# SolarCellX.net
KiCad netlist of a schematic drawn in EAGLE
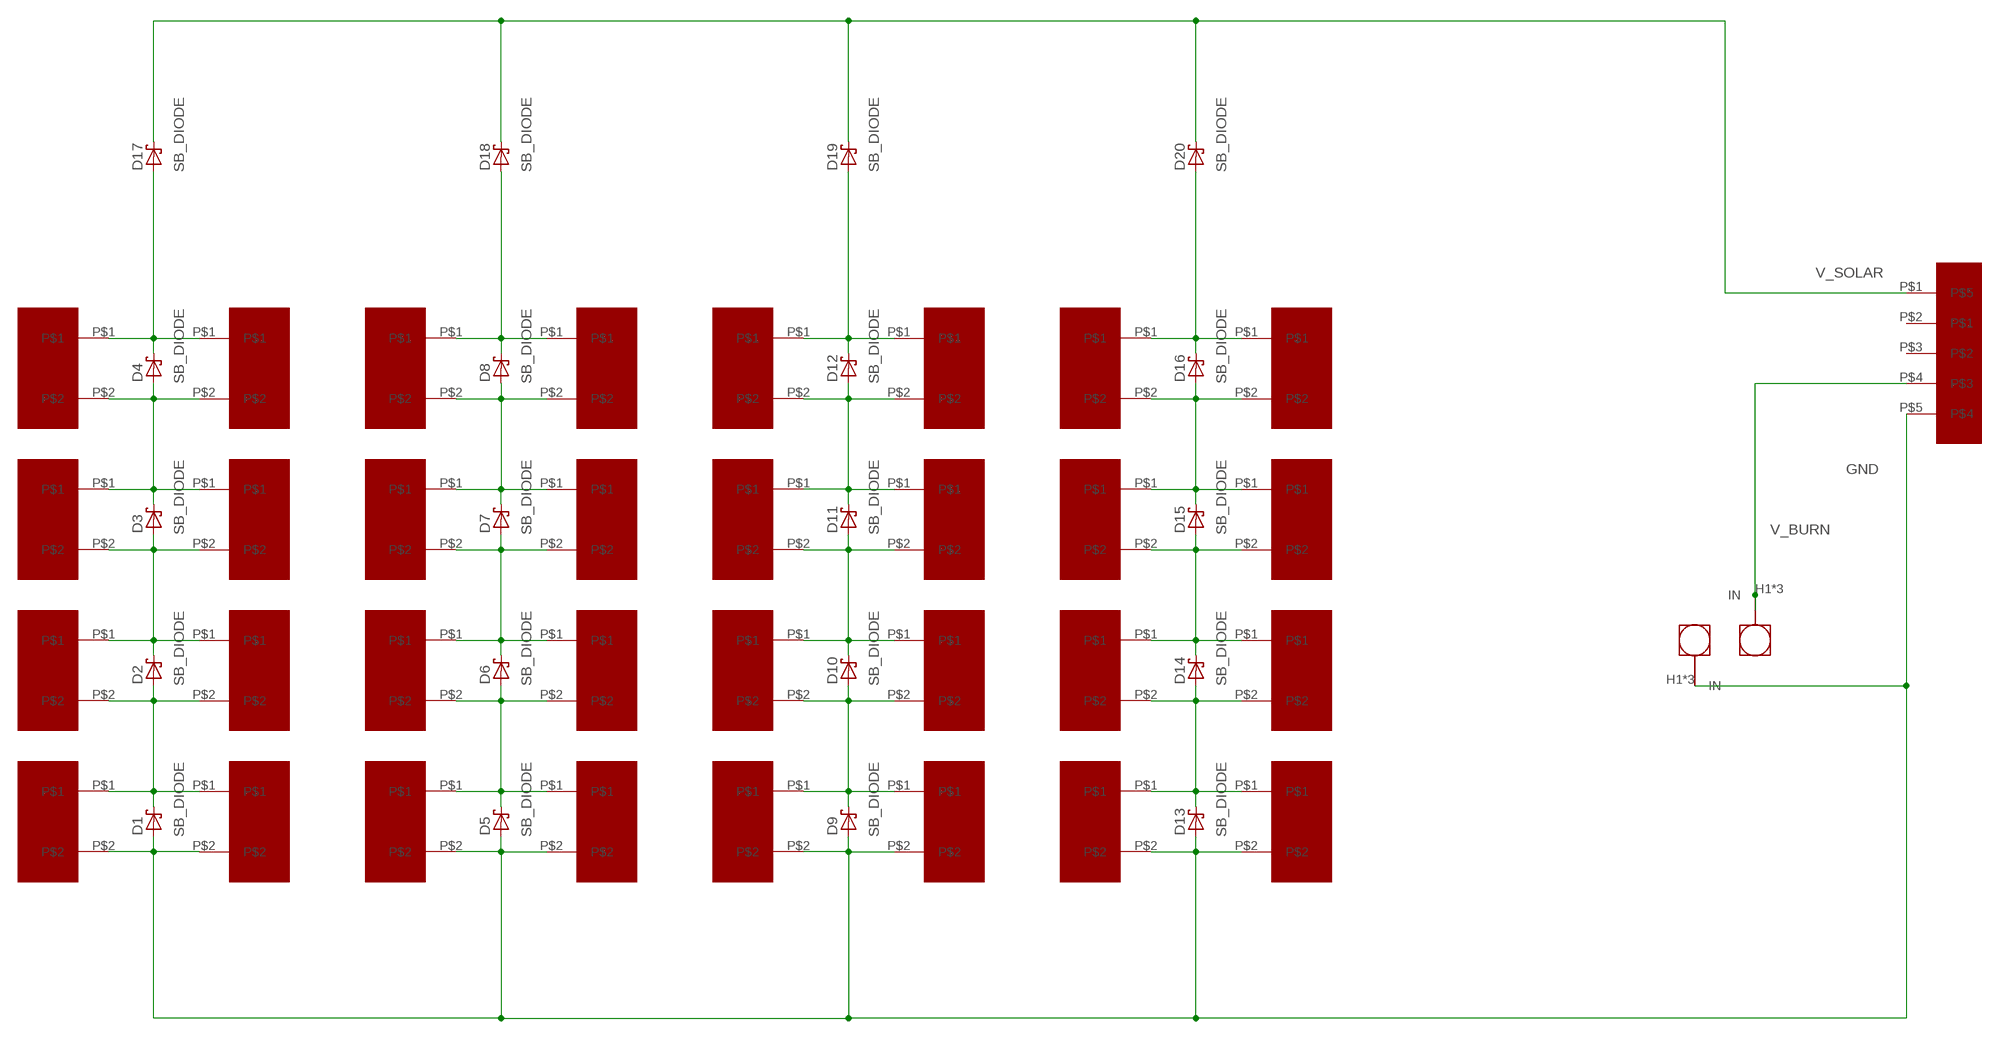
[diagram p0: schematic, sheet 1]

(export (version "E")
  (design (tool "Eeschema 10.0.6"))
  (components
    (comp (ref "11")
      (value "KXOB22-04X3F")
      (footprint "eagle-import:KXOB22-04X3F")
      (libsource (lib "eagle-import") (part "KXOB22-04X3F"))
    )
    (comp (ref "12")
      (value "KXOB22-04X3F")
      (footprint "eagle-import:KXOB22-04X3F")
      (libsource (lib "eagle-import") (part "KXOB22-04X3F"))
    )
    (comp (ref "13")
      (value "KXOB22-04X3F")
      (footprint "eagle-import:KXOB22-04X3F")
      (libsource (lib "eagle-import") (part "KXOB22-04X3F"))
    )
    (comp (ref "14")
      (value "KXOB22-04X3F")
      (footprint "eagle-import:KXOB22-04X3F")
      (libsource (lib "eagle-import") (part "KXOB22-04X3F"))
    )
    (comp (ref "15")
      (value "KXOB22-04X3F")
      (footprint "eagle-import:KXOB22-04X3F")
      (libsource (lib "eagle-import") (part "KXOB22-04X3F"))
    )
    (comp (ref "16")
      (value "KXOB22-04X3F")
      (footprint "eagle-import:KXOB22-04X3F")
      (libsource (lib "eagle-import") (part "KXOB22-04X3F"))
    )
    (comp (ref "17")
      (value "KXOB22-04X3F")
      (footprint "eagle-import:KXOB22-04X3F")
      (libsource (lib "eagle-import") (part "KXOB22-04X3F"))
    )
    (comp (ref "18")
      (value "KXOB22-04X3F")
      (footprint "eagle-import:KXOB22-04X3F")
      (libsource (lib "eagle-import") (part "KXOB22-04X3F"))
    )
    (comp (ref "21")
      (value "KXOB22-04X3F")
      (footprint "eagle-import:KXOB22-04X3F")
      (libsource (lib "eagle-import") (part "KXOB22-04X3F"))
    )
    (comp (ref "22")
      (value "KXOB22-04X3F")
      (footprint "eagle-import:KXOB22-04X3F")
      (libsource (lib "eagle-import") (part "KXOB22-04X3F"))
    )
    (comp (ref "23")
      (value "KXOB22-04X3F")
      (footprint "eagle-import:KXOB22-04X3F")
      (libsource (lib "eagle-import") (part "KXOB22-04X3F"))
    )
    (comp (ref "24")
      (value "KXOB22-04X3F")
      (footprint "eagle-import:KXOB22-04X3F")
      (libsource (lib "eagle-import") (part "KXOB22-04X3F"))
    )
    (comp (ref "25")
      (value "KXOB22-04X3F")
      (footprint "eagle-import:KXOB22-04X3F")
      (libsource (lib "eagle-import") (part "KXOB22-04X3F"))
    )
    (comp (ref "26")
      (value "KXOB22-04X3F")
      (footprint "eagle-import:KXOB22-04X3F")
      (libsource (lib "eagle-import") (part "KXOB22-04X3F"))
    )
    (comp (ref "27")
      (value "KXOB22-04X3F")
      (footprint "eagle-import:KXOB22-04X3F")
      (libsource (lib "eagle-import") (part "KXOB22-04X3F"))
    )
    (comp (ref "28")
      (value "KXOB22-04X3F")
      (footprint "eagle-import:KXOB22-04X3F")
      (libsource (lib "eagle-import") (part "KXOB22-04X3F"))
    )
    (comp (ref "31")
      (value "KXOB22-04X3F")
      (footprint "eagle-import:KXOB22-04X3F")
      (libsource (lib "eagle-import") (part "KXOB22-04X3F"))
    )
    (comp (ref "32")
      (value "KXOB22-04X3F")
      (footprint "eagle-import:KXOB22-04X3F")
      (libsource (lib "eagle-import") (part "KXOB22-04X3F"))
    )
    (comp (ref "33")
      (value "KXOB22-04X3F")
      (footprint "eagle-import:KXOB22-04X3F")
      (libsource (lib "eagle-import") (part "KXOB22-04X3F"))
    )
    (comp (ref "34")
      (value "KXOB22-04X3F")
      (footprint "eagle-import:KXOB22-04X3F")
      (libsource (lib "eagle-import") (part "KXOB22-04X3F"))
    )
    (comp (ref "35")
      (value "KXOB22-04X3F")
      (footprint "eagle-import:KXOB22-04X3F")
      (libsource (lib "eagle-import") (part "KXOB22-04X3F"))
    )
    (comp (ref "36")
      (value "KXOB22-04X3F")
      (footprint "eagle-import:KXOB22-04X3F")
      (libsource (lib "eagle-import") (part "KXOB22-04X3F"))
    )
    (comp (ref "37")
      (value "KXOB22-04X3F")
      (footprint "eagle-import:KXOB22-04X3F")
      (libsource (lib "eagle-import") (part "KXOB22-04X3F"))
    )
    (comp (ref "38")
      (value "KXOB22-04X3F")
      (footprint "eagle-import:KXOB22-04X3F")
      (libsource (lib "eagle-import") (part "KXOB22-04X3F"))
    )
    (comp (ref "41")
      (value "KXOB22-04X3F")
      (footprint "eagle-import:KXOB22-04X3F")
      (libsource (lib "eagle-import") (part "KXOB22-04X3F"))
    )
    (comp (ref "42")
      (value "KXOB22-04X3F")
      (footprint "eagle-import:KXOB22-04X3F")
      (libsource (lib "eagle-import") (part "KXOB22-04X3F"))
    )
    (comp (ref "43")
      (value "KXOB22-04X3F")
      (footprint "eagle-import:KXOB22-04X3F")
      (libsource (lib "eagle-import") (part "KXOB22-04X3F"))
    )
    (comp (ref "44")
      (value "KXOB22-04X3F")
      (footprint "eagle-import:KXOB22-04X3F")
      (libsource (lib "eagle-import") (part "KXOB22-04X3F"))
    )
    (comp (ref "45")
      (value "KXOB22-04X3F")
      (footprint "eagle-import:KXOB22-04X3F")
      (libsource (lib "eagle-import") (part "KXOB22-04X3F"))
    )
    (comp (ref "46")
      (value "KXOB22-04X3F")
      (footprint "eagle-import:KXOB22-04X3F")
      (libsource (lib "eagle-import") (part "KXOB22-04X3F"))
    )
    (comp (ref "47")
      (value "KXOB22-04X3F")
      (footprint "eagle-import:KXOB22-04X3F")
      (libsource (lib "eagle-import") (part "KXOB22-04X3F"))
    )
    (comp (ref "48")
      (value "KXOB22-04X3F")
      (footprint "eagle-import:KXOB22-04X3F")
      (libsource (lib "eagle-import") (part "KXOB22-04X3F"))
    )
    (comp (ref "D1")
      (value "SB_DIODE")
      (footprint "eagle-import:SB_DIODE")
      (libsource (lib "eagle-import") (part "SB_DIODE"))
    )
    (comp (ref "D2")
      (value "SB_DIODE")
      (footprint "eagle-import:SB_DIODE")
      (libsource (lib "eagle-import") (part "SB_DIODE"))
    )
    (comp (ref "D3")
      (value "SB_DIODE")
      (footprint "eagle-import:SB_DIODE")
      (libsource (lib "eagle-import") (part "SB_DIODE"))
    )
    (comp (ref "D4")
      (value "SB_DIODE")
      (footprint "eagle-import:SB_DIODE")
      (libsource (lib "eagle-import") (part "SB_DIODE"))
    )
    (comp (ref "D5")
      (value "SB_DIODE")
      (footprint "eagle-import:SB_DIODE")
      (libsource (lib "eagle-import") (part "SB_DIODE"))
    )
    (comp (ref "D6")
      (value "SB_DIODE")
      (footprint "eagle-import:SB_DIODE")
      (libsource (lib "eagle-import") (part "SB_DIODE"))
    )
    (comp (ref "D7")
      (value "SB_DIODE")
      (footprint "eagle-import:SB_DIODE")
      (libsource (lib "eagle-import") (part "SB_DIODE"))
    )
    (comp (ref "D8")
      (value "SB_DIODE")
      (footprint "eagle-import:SB_DIODE")
      (libsource (lib "eagle-import") (part "SB_DIODE"))
    )
    (comp (ref "D9")
      (value "SB_DIODE")
      (footprint "eagle-import:SB_DIODE")
      (libsource (lib "eagle-import") (part "SB_DIODE"))
    )
    (comp (ref "D10")
      (value "SB_DIODE")
      (footprint "eagle-import:SB_DIODE")
      (libsource (lib "eagle-import") (part "SB_DIODE"))
    )
    (comp (ref "D11")
      (value "SB_DIODE")
      (footprint "eagle-import:SB_DIODE")
      (libsource (lib "eagle-import") (part "SB_DIODE"))
    )
    (comp (ref "D12")
      (value "SB_DIODE")
      (footprint "eagle-import:SB_DIODE")
      (libsource (lib "eagle-import") (part "SB_DIODE"))
    )
    (comp (ref "D13")
      (value "SB_DIODE")
      (footprint "eagle-import:SB_DIODE")
      (libsource (lib "eagle-import") (part "SB_DIODE"))
    )
    (comp (ref "D14")
      (value "SB_DIODE")
      (footprint "eagle-import:SB_DIODE")
      (libsource (lib "eagle-import") (part "SB_DIODE"))
    )
    (comp (ref "D15")
      (value "SB_DIODE")
      (footprint "eagle-import:SB_DIODE")
      (libsource (lib "eagle-import") (part "SB_DIODE"))
    )
    (comp (ref "D16")
      (value "SB_DIODE")
      (footprint "eagle-import:SB_DIODE")
      (libsource (lib "eagle-import") (part "SB_DIODE"))
    )
    (comp (ref "D17")
      (value "SB_DIODE")
      (footprint "eagle-import:SB_DIODE")
      (libsource (lib "eagle-import") (part "SB_DIODE"))
    )
    (comp (ref "D18")
      (value "SB_DIODE")
      (footprint "eagle-import:SB_DIODE")
      (libsource (lib "eagle-import") (part "SB_DIODE"))
    )
    (comp (ref "D19")
      (value "SB_DIODE")
      (footprint "eagle-import:SB_DIODE")
      (libsource (lib "eagle-import") (part "SB_DIODE"))
    )
    (comp (ref "D20")
      (value "SB_DIODE")
      (footprint "eagle-import:SB_DIODE")
      (libsource (lib "eagle-import") (part "SB_DIODE"))
    )
    (comp (ref "U$33")
      (value "B5B-EH-A(LF)(SN)")
      (footprint "eagle-import:B5B-EH-A(LF)(SN)")
      (libsource (lib "eagle-import") (part "B5B-EH-A(LF)(SN)"))
    )
    (comp (ref "U$34")
      (value "BURNER")
      (footprint "eagle-import:BURNER")
      (libsource (lib "eagle-import") (part "BURNER"))
    )
    (comp (ref "U$35")
      (value "BURNER")
      (footprint "eagle-import:BURNER")
      (libsource (lib "eagle-import") (part "BURNER"))
    )
  )
  (nets
    (net (code "1") (name "/GND") (class "Default")
      (node (ref "11") (pin "P$2") (pinfunction "P$2_P$2") (pintype "bidirectional"))
      (node (ref "12") (pin "P$2") (pinfunction "P$2_P$2") (pintype "bidirectional"))
      (node (ref "21") (pin "P$2") (pinfunction "P$2_P$2") (pintype "bidirectional"))
      (node (ref "22") (pin "P$2") (pinfunction "P$2_P$2") (pintype "bidirectional"))
      (node (ref "31") (pin "P$2") (pinfunction "P$2_P$2") (pintype "bidirectional"))
      (node (ref "32") (pin "P$2") (pinfunction "P$2_P$2") (pintype "bidirectional"))
      (node (ref "41") (pin "P$2") (pinfunction "P$2_P$2") (pintype "bidirectional"))
      (node (ref "42") (pin "P$2") (pinfunction "P$2_P$2") (pintype "bidirectional"))
      (node (ref "D1") (pin "POS") (pinfunction "POS_POS") (pintype "passive"))
      (node (ref "D13") (pin "POS") (pinfunction "POS_POS") (pintype "passive"))
      (node (ref "D5") (pin "POS") (pinfunction "POS_POS") (pintype "passive"))
      (node (ref "D9") (pin "POS") (pinfunction "POS_POS") (pintype "passive"))
      (node (ref "U$33") (pin "P$5") (pinfunction "P$4_P$5") (pintype "bidirectional"))
      (node (ref "U$35") (pin "H1") (pinfunction "IN_H1") (pintype "bidirectional"))
      (node (ref "U$35") (pin "H2") (pinfunction "IN_H2") (pintype "bidirectional"))
      (node (ref "U$35") (pin "H3") (pinfunction "IN_H3") (pintype "bidirectional"))
    )
    (net (code "2") (name "/V_BURN") (class "Default")
      (node (ref "U$33") (pin "P$4") (pinfunction "P$3_P$4") (pintype "bidirectional"))
      (node (ref "U$34") (pin "H1") (pinfunction "IN_H1") (pintype "bidirectional"))
      (node (ref "U$34") (pin "H2") (pinfunction "IN_H2") (pintype "bidirectional"))
      (node (ref "U$34") (pin "H3") (pinfunction "IN_H3") (pintype "bidirectional"))
    )
    (net (code "3") (name "/V_SOLAR") (class "Default")
      (node (ref "D17") (pin "NEG") (pinfunction "NEG_NEG") (pintype "passive"))
      (node (ref "D18") (pin "NEG") (pinfunction "NEG_NEG") (pintype "passive"))
      (node (ref "D19") (pin "NEG") (pinfunction "NEG_NEG") (pintype "passive"))
      (node (ref "D20") (pin "NEG") (pinfunction "NEG_NEG") (pintype "passive"))
      (node (ref "U$33") (pin "P$1") (pinfunction "P$5_P$1") (pintype "bidirectional"))
    )
    (net (code "4") (name "Net-(11-PadP$1)") (class "Default")
      (node (ref "11") (pin "P$1") (pinfunction "P$1_P$1") (pintype "bidirectional"))
      (node (ref "12") (pin "P$1") (pinfunction "P$1_P$1") (pintype "bidirectional"))
      (node (ref "13") (pin "P$2") (pinfunction "P$2_P$2") (pintype "bidirectional"))
      (node (ref "14") (pin "P$2") (pinfunction "P$2_P$2") (pintype "bidirectional"))
      (node (ref "D1") (pin "NEG") (pinfunction "NEG_NEG") (pintype "passive"))
      (node (ref "D2") (pin "POS") (pinfunction "POS_POS") (pintype "passive"))
    )
    (net (code "5") (name "Net-(13-PadP$1)") (class "Default")
      (node (ref "13") (pin "P$1") (pinfunction "P$1_P$1") (pintype "bidirectional"))
      (node (ref "14") (pin "P$1") (pinfunction "P$1_P$1") (pintype "bidirectional"))
      (node (ref "15") (pin "P$2") (pinfunction "P$2_P$2") (pintype "bidirectional"))
      (node (ref "16") (pin "P$2") (pinfunction "P$2_P$2") (pintype "bidirectional"))
      (node (ref "D2") (pin "NEG") (pinfunction "NEG_NEG") (pintype "passive"))
      (node (ref "D3") (pin "POS") (pinfunction "POS_POS") (pintype "passive"))
    )
    (net (code "6") (name "Net-(15-PadP$1)") (class "Default")
      (node (ref "15") (pin "P$1") (pinfunction "P$1_P$1") (pintype "bidirectional"))
      (node (ref "16") (pin "P$1") (pinfunction "P$1_P$1") (pintype "bidirectional"))
      (node (ref "17") (pin "P$2") (pinfunction "P$2_P$2") (pintype "bidirectional"))
      (node (ref "18") (pin "P$2") (pinfunction "P$2_P$2") (pintype "bidirectional"))
      (node (ref "D3") (pin "NEG") (pinfunction "NEG_NEG") (pintype "passive"))
      (node (ref "D4") (pin "POS") (pinfunction "POS_POS") (pintype "passive"))
    )
    (net (code "7") (name "Net-(17-PadP$1)") (class "Default")
      (node (ref "17") (pin "P$1") (pinfunction "P$1_P$1") (pintype "bidirectional"))
      (node (ref "18") (pin "P$1") (pinfunction "P$1_P$1") (pintype "bidirectional"))
      (node (ref "D17") (pin "POS") (pinfunction "POS_POS") (pintype "passive"))
      (node (ref "D4") (pin "NEG") (pinfunction "NEG_NEG") (pintype "passive"))
    )
    (net (code "8") (name "Net-(21-PadP$1)") (class "Default")
      (node (ref "21") (pin "P$1") (pinfunction "P$1_P$1") (pintype "bidirectional"))
      (node (ref "22") (pin "P$1") (pinfunction "P$1_P$1") (pintype "bidirectional"))
      (node (ref "23") (pin "P$2") (pinfunction "P$2_P$2") (pintype "bidirectional"))
      (node (ref "24") (pin "P$2") (pinfunction "P$2_P$2") (pintype "bidirectional"))
      (node (ref "D5") (pin "NEG") (pinfunction "NEG_NEG") (pintype "passive"))
      (node (ref "D6") (pin "POS") (pinfunction "POS_POS") (pintype "passive"))
    )
    (net (code "9") (name "Net-(23-PadP$1)") (class "Default")
      (node (ref "23") (pin "P$1") (pinfunction "P$1_P$1") (pintype "bidirectional"))
      (node (ref "24") (pin "P$1") (pinfunction "P$1_P$1") (pintype "bidirectional"))
      (node (ref "25") (pin "P$2") (pinfunction "P$2_P$2") (pintype "bidirectional"))
      (node (ref "26") (pin "P$2") (pinfunction "P$2_P$2") (pintype "bidirectional"))
      (node (ref "D6") (pin "NEG") (pinfunction "NEG_NEG") (pintype "passive"))
      (node (ref "D7") (pin "POS") (pinfunction "POS_POS") (pintype "passive"))
    )
    (net (code "10") (name "Net-(25-PadP$1)") (class "Default")
      (node (ref "25") (pin "P$1") (pinfunction "P$1_P$1") (pintype "bidirectional"))
      (node (ref "26") (pin "P$1") (pinfunction "P$1_P$1") (pintype "bidirectional"))
      (node (ref "27") (pin "P$2") (pinfunction "P$2_P$2") (pintype "bidirectional"))
      (node (ref "28") (pin "P$2") (pinfunction "P$2_P$2") (pintype "bidirectional"))
      (node (ref "D7") (pin "NEG") (pinfunction "NEG_NEG") (pintype "passive"))
      (node (ref "D8") (pin "POS") (pinfunction "POS_POS") (pintype "passive"))
    )
    (net (code "11") (name "Net-(27-PadP$1)") (class "Default")
      (node (ref "27") (pin "P$1") (pinfunction "P$1_P$1") (pintype "bidirectional"))
      (node (ref "28") (pin "P$1") (pinfunction "P$1_P$1") (pintype "bidirectional"))
      (node (ref "D18") (pin "POS") (pinfunction "POS_POS") (pintype "passive"))
      (node (ref "D8") (pin "NEG") (pinfunction "NEG_NEG") (pintype "passive"))
    )
    (net (code "12") (name "Net-(31-PadP$1)") (class "Default")
      (node (ref "31") (pin "P$1") (pinfunction "P$1_P$1") (pintype "bidirectional"))
      (node (ref "32") (pin "P$1") (pinfunction "P$1_P$1") (pintype "bidirectional"))
      (node (ref "33") (pin "P$2") (pinfunction "P$2_P$2") (pintype "bidirectional"))
      (node (ref "34") (pin "P$2") (pinfunction "P$2_P$2") (pintype "bidirectional"))
      (node (ref "D10") (pin "POS") (pinfunction "POS_POS") (pintype "passive"))
      (node (ref "D9") (pin "NEG") (pinfunction "NEG_NEG") (pintype "passive"))
    )
    (net (code "13") (name "Net-(33-PadP$1)") (class "Default")
      (node (ref "33") (pin "P$1") (pinfunction "P$1_P$1") (pintype "bidirectional"))
      (node (ref "34") (pin "P$1") (pinfunction "P$1_P$1") (pintype "bidirectional"))
      (node (ref "35") (pin "P$2") (pinfunction "P$2_P$2") (pintype "bidirectional"))
      (node (ref "36") (pin "P$2") (pinfunction "P$2_P$2") (pintype "bidirectional"))
      (node (ref "D10") (pin "NEG") (pinfunction "NEG_NEG") (pintype "passive"))
      (node (ref "D11") (pin "POS") (pinfunction "POS_POS") (pintype "passive"))
    )
    (net (code "14") (name "Net-(35-PadP$1)") (class "Default")
      (node (ref "35") (pin "P$1") (pinfunction "P$1_P$1") (pintype "bidirectional"))
      (node (ref "36") (pin "P$1") (pinfunction "P$1_P$1") (pintype "bidirectional"))
      (node (ref "37") (pin "P$2") (pinfunction "P$2_P$2") (pintype "bidirectional"))
      (node (ref "38") (pin "P$2") (pinfunction "P$2_P$2") (pintype "bidirectional"))
      (node (ref "D11") (pin "NEG") (pinfunction "NEG_NEG") (pintype "passive"))
      (node (ref "D12") (pin "POS") (pinfunction "POS_POS") (pintype "passive"))
    )
    (net (code "15") (name "Net-(37-PadP$1)") (class "Default")
      (node (ref "37") (pin "P$1") (pinfunction "P$1_P$1") (pintype "bidirectional"))
      (node (ref "38") (pin "P$1") (pinfunction "P$1_P$1") (pintype "bidirectional"))
      (node (ref "D12") (pin "NEG") (pinfunction "NEG_NEG") (pintype "passive"))
      (node (ref "D19") (pin "POS") (pinfunction "POS_POS") (pintype "passive"))
    )
    (net (code "16") (name "Net-(41-PadP$1)") (class "Default")
      (node (ref "41") (pin "P$1") (pinfunction "P$1_P$1") (pintype "bidirectional"))
      (node (ref "42") (pin "P$1") (pinfunction "P$1_P$1") (pintype "bidirectional"))
      (node (ref "43") (pin "P$2") (pinfunction "P$2_P$2") (pintype "bidirectional"))
      (node (ref "44") (pin "P$2") (pinfunction "P$2_P$2") (pintype "bidirectional"))
      (node (ref "D13") (pin "NEG") (pinfunction "NEG_NEG") (pintype "passive"))
      (node (ref "D14") (pin "POS") (pinfunction "POS_POS") (pintype "passive"))
    )
    (net (code "17") (name "Net-(43-PadP$1)") (class "Default")
      (node (ref "43") (pin "P$1") (pinfunction "P$1_P$1") (pintype "bidirectional"))
      (node (ref "44") (pin "P$1") (pinfunction "P$1_P$1") (pintype "bidirectional"))
      (node (ref "45") (pin "P$2") (pinfunction "P$2_P$2") (pintype "bidirectional"))
      (node (ref "46") (pin "P$2") (pinfunction "P$2_P$2") (pintype "bidirectional"))
      (node (ref "D14") (pin "NEG") (pinfunction "NEG_NEG") (pintype "passive"))
      (node (ref "D15") (pin "POS") (pinfunction "POS_POS") (pintype "passive"))
    )
    (net (code "18") (name "Net-(45-PadP$1)") (class "Default")
      (node (ref "45") (pin "P$1") (pinfunction "P$1_P$1") (pintype "bidirectional"))
      (node (ref "46") (pin "P$1") (pinfunction "P$1_P$1") (pintype "bidirectional"))
      (node (ref "47") (pin "P$2") (pinfunction "P$2_P$2") (pintype "bidirectional"))
      (node (ref "48") (pin "P$2") (pinfunction "P$2_P$2") (pintype "bidirectional"))
      (node (ref "D15") (pin "NEG") (pinfunction "NEG_NEG") (pintype "passive"))
      (node (ref "D16") (pin "POS") (pinfunction "POS_POS") (pintype "passive"))
    )
    (net (code "19") (name "Net-(47-PadP$1)") (class "Default")
      (node (ref "47") (pin "P$1") (pinfunction "P$1_P$1") (pintype "bidirectional"))
      (node (ref "48") (pin "P$1") (pinfunction "P$1_P$1") (pintype "bidirectional"))
      (node (ref "D16") (pin "NEG") (pinfunction "NEG_NEG") (pintype "passive"))
      (node (ref "D20") (pin "POS") (pinfunction "POS_POS") (pintype "passive"))
    )
    (net (code "20") (name "unconnected-(U$33-P$1-PadP$2)") (class "Default")
      (node (ref "U$33") (pin "P$2") (pinfunction "P$1_P$2") (pintype "bidirectional"))
    )
    (net (code "21") (name "unconnected-(U$33-P$2-PadP$3)") (class "Default")
      (node (ref "U$33") (pin "P$3") (pinfunction "P$2_P$3") (pintype "bidirectional"))
    )
  )
)
